# 06_mPCIe_1-4.net
KiCad netlist of a schematic drawn in Altium Designer
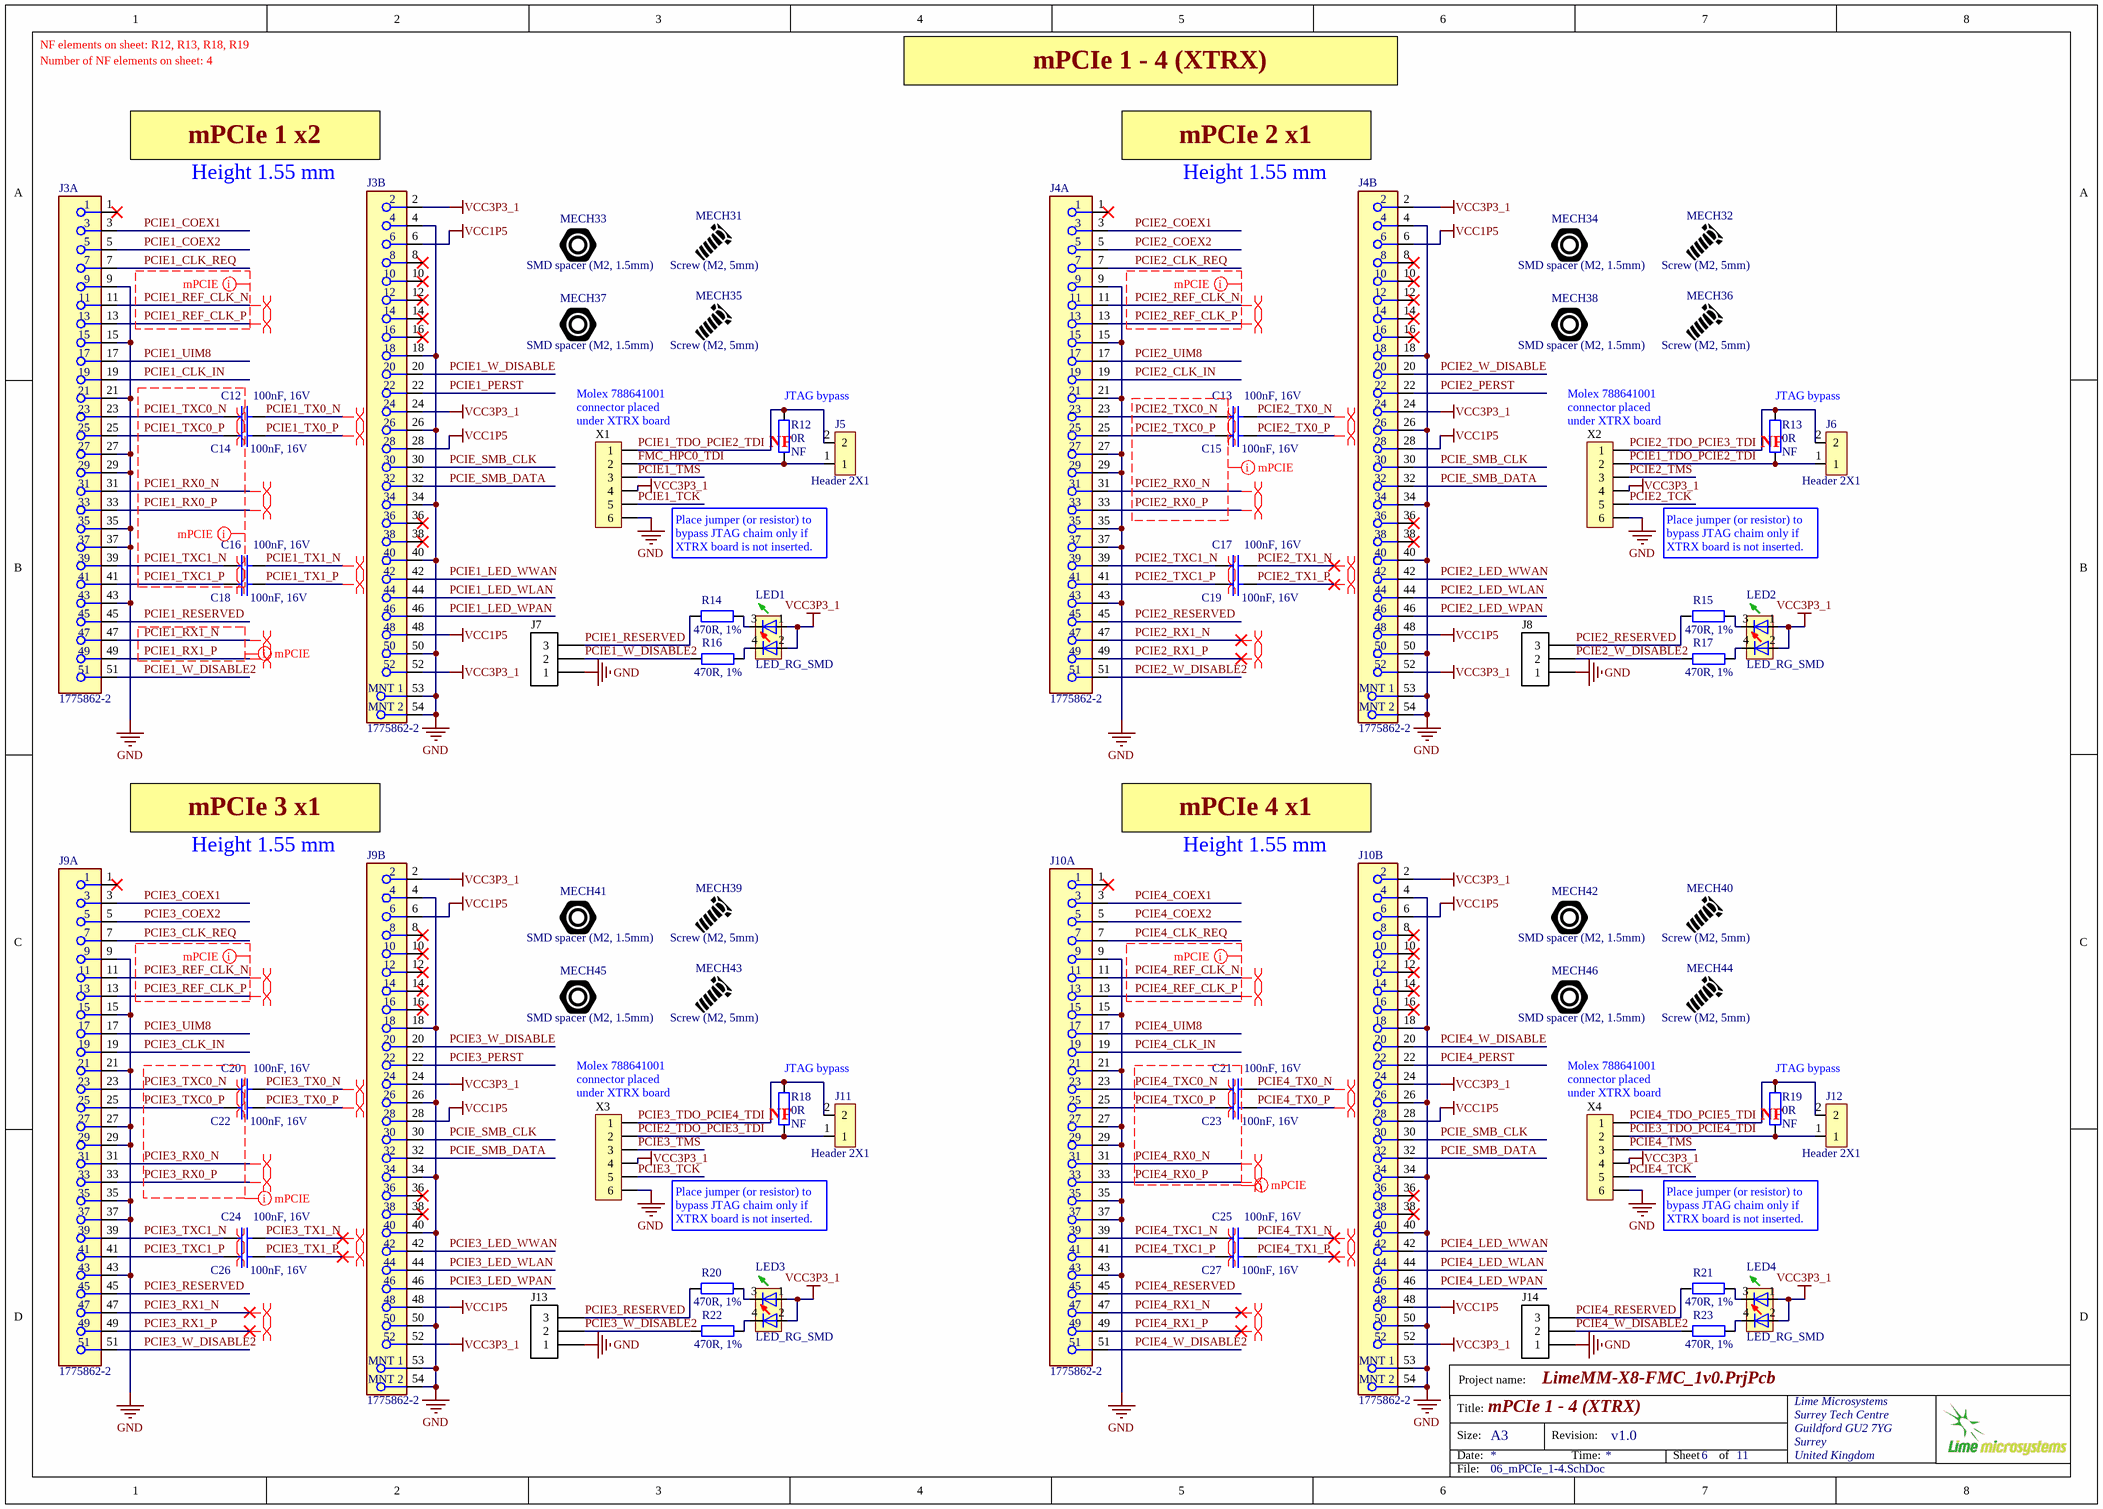
[diagram p0: 06_mPCIe_1-4.SchDoc]

(export (version "E")
  (design (tool "Eeschema 10.0.6"))
  (components
    (comp (ref "C12")
      (value "100nF, 16V")
      (footprint "CAP0402")
      (fields
        (field (name "MANUFACTURER") "Murata Electronics")
        (field (name "TOLERANCE") "10 %")
        (field (name "MANUFACTURER PART NUMBER") "GRM155R71C104KA88D")
      )
      (libsource (lib "LimeMicroAltiumLib_schLib") (part "Cap_0402"))
    )
    (comp (ref "C13")
      (value "100nF, 16V")
      (footprint "CAP0402")
      (fields
        (field (name "MANUFACTURER") "Murata Electronics")
        (field (name "TOLERANCE") "10 %")
        (field (name "MANUFACTURER PART NUMBER") "GRM155R71C104KA88D")
      )
      (libsource (lib "LimeMicroAltiumLib_schLib") (part "Cap_0402"))
    )
    (comp (ref "C14")
      (value "100nF, 16V")
      (footprint "CAP0402")
      (fields
        (field (name "MANUFACTURER") "Murata Electronics")
        (field (name "TOLERANCE") "10 %")
        (field (name "MANUFACTURER PART NUMBER") "GRM155R71C104KA88D")
      )
      (libsource (lib "LimeMicroAltiumLib_schLib") (part "Cap_0402"))
    )
    (comp (ref "C15")
      (value "100nF, 16V")
      (footprint "CAP0402")
      (fields
        (field (name "MANUFACTURER") "Murata Electronics")
        (field (name "TOLERANCE") "10 %")
        (field (name "MANUFACTURER PART NUMBER") "GRM155R71C104KA88D")
      )
      (libsource (lib "LimeMicroAltiumLib_schLib") (part "Cap_0402"))
    )
    (comp (ref "C16")
      (value "100nF, 16V")
      (footprint "CAP0402")
      (fields
        (field (name "MANUFACTURER") "Murata Electronics")
        (field (name "TOLERANCE") "10 %")
        (field (name "MANUFACTURER PART NUMBER") "GRM155R71C104KA88D")
      )
      (libsource (lib "LimeMicroAltiumLib_schLib") (part "Cap_0402"))
    )
    (comp (ref "C17")
      (value "100nF, 16V")
      (footprint "CAP0402")
      (fields
        (field (name "MANUFACTURER") "Murata Electronics")
        (field (name "TOLERANCE") "10 %")
        (field (name "MANUFACTURER PART NUMBER") "GRM155R71C104KA88D")
      )
      (libsource (lib "LimeMicroAltiumLib_schLib") (part "Cap_0402"))
    )
    (comp (ref "C18")
      (value "100nF, 16V")
      (footprint "CAP0402")
      (fields
        (field (name "MANUFACTURER") "Murata Electronics")
        (field (name "TOLERANCE") "10 %")
        (field (name "MANUFACTURER PART NUMBER") "GRM155R71C104KA88D")
      )
      (libsource (lib "LimeMicroAltiumLib_schLib") (part "Cap_0402"))
    )
    (comp (ref "C19")
      (value "100nF, 16V")
      (footprint "CAP0402")
      (fields
        (field (name "MANUFACTURER") "Murata Electronics")
        (field (name "TOLERANCE") "10 %")
        (field (name "MANUFACTURER PART NUMBER") "GRM155R71C104KA88D")
      )
      (libsource (lib "LimeMicroAltiumLib_schLib") (part "Cap_0402"))
    )
    (comp (ref "C20")
      (value "100nF, 16V")
      (footprint "CAP0402")
      (fields
        (field (name "MANUFACTURER") "Murata Electronics")
        (field (name "TOLERANCE") "10 %")
        (field (name "MANUFACTURER PART NUMBER") "GRM155R71C104KA88D")
      )
      (libsource (lib "LimeMicroAltiumLib_schLib") (part "Cap_0402"))
    )
    (comp (ref "C21")
      (value "100nF, 16V")
      (footprint "CAP0402")
      (fields
        (field (name "MANUFACTURER") "Murata Electronics")
        (field (name "TOLERANCE") "10 %")
        (field (name "MANUFACTURER PART NUMBER") "GRM155R71C104KA88D")
      )
      (libsource (lib "LimeMicroAltiumLib_schLib") (part "Cap_0402"))
    )
    (comp (ref "C22")
      (value "100nF, 16V")
      (footprint "CAP0402")
      (fields
        (field (name "MANUFACTURER") "Murata Electronics")
        (field (name "TOLERANCE") "10 %")
        (field (name "MANUFACTURER PART NUMBER") "GRM155R71C104KA88D")
      )
      (libsource (lib "LimeMicroAltiumLib_schLib") (part "Cap_0402"))
    )
    (comp (ref "C23")
      (value "100nF, 16V")
      (footprint "CAP0402")
      (fields
        (field (name "MANUFACTURER") "Murata Electronics")
        (field (name "TOLERANCE") "10 %")
        (field (name "MANUFACTURER PART NUMBER") "GRM155R71C104KA88D")
      )
      (libsource (lib "LimeMicroAltiumLib_schLib") (part "Cap_0402"))
    )
    (comp (ref "C24")
      (value "100nF, 16V")
      (footprint "CAP0402")
      (fields
        (field (name "MANUFACTURER") "Murata Electronics")
        (field (name "TOLERANCE") "10 %")
        (field (name "MANUFACTURER PART NUMBER") "GRM155R71C104KA88D")
      )
      (libsource (lib "LimeMicroAltiumLib_schLib") (part "Cap_0402"))
    )
    (comp (ref "C25")
      (value "100nF, 16V")
      (footprint "CAP0402")
      (fields
        (field (name "MANUFACTURER") "Murata Electronics")
        (field (name "TOLERANCE") "10 %")
        (field (name "MANUFACTURER PART NUMBER") "GRM155R71C104KA88D")
      )
      (libsource (lib "LimeMicroAltiumLib_schLib") (part "Cap_0402"))
    )
    (comp (ref "C26")
      (value "100nF, 16V")
      (footprint "CAP0402")
      (fields
        (field (name "MANUFACTURER") "Murata Electronics")
        (field (name "TOLERANCE") "10 %")
        (field (name "MANUFACTURER PART NUMBER") "GRM155R71C104KA88D")
      )
      (libsource (lib "LimeMicroAltiumLib_schLib") (part "Cap_0402"))
    )
    (comp (ref "C27")
      (value "100nF, 16V")
      (footprint "CAP0402")
      (fields
        (field (name "MANUFACTURER") "Murata Electronics")
        (field (name "TOLERANCE") "10 %")
        (field (name "MANUFACTURER PART NUMBER") "GRM155R71C104KA88D")
      )
      (libsource (lib "LimeMicroAltiumLib_schLib") (part "Cap_0402"))
    )
    (comp (ref "J3")
      (value "1775862-2")
      (footprint "MiniPCIe_connector_XTRX")
      (description "CONN PCI EXP MINI FEMALE 52POS")
      (fields (field (name "MANUFACTURER") "JAE Electronics"))
      (libsource (lib "LimeMicroAltiumLib_schLib_r04") (part "MINI_PCIE_FEMALE"))
    )
    (comp (ref "J4")
      (value "1775862-2")
      (footprint "MiniPCIe_connector_XTRX")
      (description "CONN PCI EXP MINI FEMALE 52POS")
      (fields (field (name "MANUFACTURER") "JAE Electronics"))
      (libsource (lib "LimeMicroAltiumLib_schLib_r04") (part "MINI_PCIE_FEMALE"))
    )
    (comp (ref "J5")
      (value "Header 2X1")
      (footprint "HDR_1x2")
      (fields (field (name "MANUFACTURER") "3M"))
      (libsource (lib "LimeFPGAboard_schLib") (part "Jumper"))
    )
    (comp (ref "J6")
      (value "Header 2X1")
      (footprint "HDR_1x2")
      (fields (field (name "MANUFACTURER") "3M"))
      (libsource (lib "LimeFPGAboard_schLib") (part "Jumper"))
    )
    (comp (ref "J7")
      (value "Header 3x1 pin")
      (footprint "HDR_1x3")
      (description "Header, 3-pin")
      (fields
        (field (name "MANUFACTURER PART NUMBER") "61300311121")
        (field (name "MANUFACTURER") "Wurth Electronics")
      )
      (libsource (lib "LimeMicroAltiumLib_schLib_r04") (part "Header3P"))
    )
    (comp (ref "J8")
      (value "Header 3x1 pin")
      (footprint "HDR_1x3")
      (description "Header, 3-pin")
      (fields
        (field (name "MANUFACTURER PART NUMBER") "61300311121")
        (field (name "MANUFACTURER") "Wurth Electronics")
      )
      (libsource (lib "LimeMicroAltiumLib_schLib_r04") (part "Header3P"))
    )
    (comp (ref "J9")
      (value "1775862-2")
      (footprint "MiniPCIe_connector_XTRX")
      (description "CONN PCI EXP MINI FEMALE 52POS")
      (fields (field (name "MANUFACTURER") "JAE Electronics"))
      (libsource (lib "LimeMicroAltiumLib_schLib_r04") (part "MINI_PCIE_FEMALE"))
    )
    (comp (ref "J10")
      (value "1775862-2")
      (footprint "MiniPCIe_connector_XTRX")
      (description "CONN PCI EXP MINI FEMALE 52POS")
      (fields (field (name "MANUFACTURER") "JAE Electronics"))
      (libsource (lib "LimeMicroAltiumLib_schLib_r04") (part "MINI_PCIE_FEMALE"))
    )
    (comp (ref "J11")
      (value "Header 2X1")
      (footprint "HDR_1x2")
      (fields (field (name "MANUFACTURER") "3M"))
      (libsource (lib "LimeFPGAboard_schLib") (part "Jumper"))
    )
    (comp (ref "J12")
      (value "Header 2X1")
      (footprint "HDR_1x2")
      (fields (field (name "MANUFACTURER") "3M"))
      (libsource (lib "LimeFPGAboard_schLib") (part "Jumper"))
    )
    (comp (ref "J13")
      (value "Header 3x1 pin")
      (footprint "HDR_1x3")
      (description "Header, 3-pin")
      (fields
        (field (name "MANUFACTURER PART NUMBER") "61300311121")
        (field (name "MANUFACTURER") "Wurth Electronics")
      )
      (libsource (lib "LimeMicroAltiumLib_schLib_r04") (part "Header3P"))
    )
    (comp (ref "J14")
      (value "Header 3x1 pin")
      (footprint "HDR_1x3")
      (description "Header, 3-pin")
      (fields
        (field (name "MANUFACTURER PART NUMBER") "61300311121")
        (field (name "MANUFACTURER") "Wurth Electronics")
      )
      (libsource (lib "LimeMicroAltiumLib_schLib_r04") (part "Header3P"))
    )
    (comp (ref "LED1")
      (value "LED_RG_SMD")
      (footprint "LED-2x0603")
      (fields (field (name "MANUFACTURER") "Avago Technologies US Inc."))
      (libsource (lib "LimeMicroAltiumLib_schLib") (part "LED_green_red_SMD"))
    )
    (comp (ref "LED2")
      (value "LED_RG_SMD")
      (footprint "LED-2x0603")
      (fields (field (name "MANUFACTURER") "Avago Technologies US Inc."))
      (libsource (lib "LimeMicroAltiumLib_schLib") (part "LED_green_red_SMD"))
    )
    (comp (ref "LED3")
      (value "LED_RG_SMD")
      (footprint "LED-2x0603")
      (fields (field (name "MANUFACTURER") "Avago Technologies US Inc."))
      (libsource (lib "LimeMicroAltiumLib_schLib") (part "LED_green_red_SMD"))
    )
    (comp (ref "LED4")
      (value "LED_RG_SMD")
      (footprint "LED-2x0603")
      (fields (field (name "MANUFACTURER") "Avago Technologies US Inc."))
      (libsource (lib "LimeMicroAltiumLib_schLib") (part "LED_green_red_SMD"))
    )
    (comp (ref "MECH31")
      (value "Screw (M2, 5mm)")
      (fields (field (name "MANUFACTURER") "B&F Fastener"))
      (libsource (lib "LimeMicroAltiumLib_schLib_r05") (part "Universal_mech_screw"))
    )
    (comp (ref "MECH32")
      (value "Screw (M2, 5mm)")
      (fields (field (name "MANUFACTURER") "B&F Fastener"))
      (libsource (lib "LimeMicroAltiumLib_schLib_r05") (part "Universal_mech_screw"))
    )
    (comp (ref "MECH33")
      (value "SMD spacer (M2, 1.5mm)")
      (fields (field (name "MANUFACTURER") "Wurth Electronics"))
      (libsource (lib "LimeMicroAltiumLib_schLib_r05") (part "Universal_mech_nut"))
    )
    (comp (ref "MECH34")
      (value "SMD spacer (M2, 1.5mm)")
      (fields (field (name "MANUFACTURER") "Wurth Electronics"))
      (libsource (lib "LimeMicroAltiumLib_schLib_r05") (part "Universal_mech_nut"))
    )
    (comp (ref "MECH35")
      (value "Screw (M2, 5mm)")
      (fields (field (name "MANUFACTURER") "B&F Fastener"))
      (libsource (lib "LimeMicroAltiumLib_schLib_r05") (part "Universal_mech_screw"))
    )
    (comp (ref "MECH36")
      (value "Screw (M2, 5mm)")
      (fields (field (name "MANUFACTURER") "B&F Fastener"))
      (libsource (lib "LimeMicroAltiumLib_schLib_r05") (part "Universal_mech_screw"))
    )
    (comp (ref "MECH37")
      (value "SMD spacer (M2, 1.5mm)")
      (fields (field (name "MANUFACTURER") "Wurth Electronics"))
      (libsource (lib "LimeMicroAltiumLib_schLib_r05") (part "Universal_mech_nut"))
    )
    (comp (ref "MECH38")
      (value "SMD spacer (M2, 1.5mm)")
      (fields (field (name "MANUFACTURER") "Wurth Electronics"))
      (libsource (lib "LimeMicroAltiumLib_schLib_r05") (part "Universal_mech_nut"))
    )
    (comp (ref "MECH39")
      (value "Screw (M2, 5mm)")
      (fields (field (name "MANUFACTURER") "B&F Fastener"))
      (libsource (lib "LimeMicroAltiumLib_schLib_r05") (part "Universal_mech_screw"))
    )
    (comp (ref "MECH40")
      (value "Screw (M2, 5mm)")
      (fields (field (name "MANUFACTURER") "B&F Fastener"))
      (libsource (lib "LimeMicroAltiumLib_schLib_r05") (part "Universal_mech_screw"))
    )
    (comp (ref "MECH41")
      (value "SMD spacer (M2, 1.5mm)")
      (fields (field (name "MANUFACTURER") "Wurth Electronics"))
      (libsource (lib "LimeMicroAltiumLib_schLib_r05") (part "Universal_mech_nut"))
    )
    (comp (ref "MECH42")
      (value "SMD spacer (M2, 1.5mm)")
      (fields (field (name "MANUFACTURER") "Wurth Electronics"))
      (libsource (lib "LimeMicroAltiumLib_schLib_r05") (part "Universal_mech_nut"))
    )
    (comp (ref "MECH43")
      (value "Screw (M2, 5mm)")
      (fields (field (name "MANUFACTURER") "B&F Fastener"))
      (libsource (lib "LimeMicroAltiumLib_schLib_r05") (part "Universal_mech_screw"))
    )
    (comp (ref "MECH44")
      (value "Screw (M2, 5mm)")
      (fields (field (name "MANUFACTURER") "B&F Fastener"))
      (libsource (lib "LimeMicroAltiumLib_schLib_r05") (part "Universal_mech_screw"))
    )
    (comp (ref "MECH45")
      (value "SMD spacer (M2, 1.5mm)")
      (fields (field (name "MANUFACTURER") "Wurth Electronics"))
      (libsource (lib "LimeMicroAltiumLib_schLib_r05") (part "Universal_mech_nut"))
    )
    (comp (ref "MECH46")
      (value "SMD spacer (M2, 1.5mm)")
      (fields (field (name "MANUFACTURER") "Wurth Electronics"))
      (libsource (lib "LimeMicroAltiumLib_schLib_r05") (part "Universal_mech_nut"))
    )
    (comp (ref "R12")
      (value "0R")
      (footprint "RES0402")
      (fields
        (field (name "ASSEMBLY INFO") "NF")
        (field (name "MANUFACTURER") "Yageo")
        (field (name "TOLERANCE") "Jumper")
      )
      (libsource (lib "") (part "Res_0402_1"))
    )
    (comp (ref "R13")
      (value "0R")
      (footprint "RES0402")
      (fields
        (field (name "ASSEMBLY INFO") "NF")
        (field (name "MANUFACTURER") "Yageo")
        (field (name "TOLERANCE") "Jumper")
      )
      (libsource (lib "") (part "Res_0402_1"))
    )
    (comp (ref "R14")
      (value "470R, 1%")
      (footprint "RES0402")
      (fields (field (name "TOLERANCE") "1%") (field (name "MANUFACTURER") "Yageo"))
      (libsource (lib "LimeMicroAltiumLib_schLib") (part "Res_0402"))
    )
    (comp (ref "R15")
      (value "470R, 1%")
      (footprint "RES0402")
      (fields (field (name "TOLERANCE") "1%") (field (name "MANUFACTURER") "Yageo"))
      (libsource (lib "LimeMicroAltiumLib_schLib") (part "Res_0402"))
    )
    (comp (ref "R16")
      (value "470R, 1%")
      (footprint "RES0402")
      (fields (field (name "TOLERANCE") "1%") (field (name "MANUFACTURER") "Yageo"))
      (libsource (lib "LimeMicroAltiumLib_schLib") (part "Res_0402"))
    )
    (comp (ref "R17")
      (value "470R, 1%")
      (footprint "RES0402")
      (fields (field (name "TOLERANCE") "1%") (field (name "MANUFACTURER") "Yageo"))
      (libsource (lib "LimeMicroAltiumLib_schLib") (part "Res_0402"))
    )
    (comp (ref "R18")
      (value "0R")
      (footprint "RES0402")
      (fields
        (field (name "ASSEMBLY INFO") "NF")
        (field (name "MANUFACTURER") "Yageo")
        (field (name "TOLERANCE") "Jumper")
      )
      (libsource (lib "") (part "Res_0402_1"))
    )
    (comp (ref "R19")
      (value "0R")
      (footprint "RES0402")
      (fields
        (field (name "ASSEMBLY INFO") "NF")
        (field (name "MANUFACTURER") "Yageo")
        (field (name "TOLERANCE") "Jumper")
      )
      (libsource (lib "") (part "Res_0402_1"))
    )
    (comp (ref "R20")
      (value "470R, 1%")
      (footprint "RES0402")
      (fields (field (name "TOLERANCE") "1%") (field (name "MANUFACTURER") "Yageo"))
      (libsource (lib "LimeMicroAltiumLib_schLib") (part "Res_0402"))
    )
    (comp (ref "R21")
      (value "470R, 1%")
      (footprint "RES0402")
      (fields (field (name "TOLERANCE") "1%") (field (name "MANUFACTURER") "Yageo"))
      (libsource (lib "LimeMicroAltiumLib_schLib") (part "Res_0402"))
    )
    (comp (ref "R22")
      (value "470R, 1%")
      (footprint "RES0402")
      (fields (field (name "TOLERANCE") "1%") (field (name "MANUFACTURER") "Yageo"))
      (libsource (lib "LimeMicroAltiumLib_schLib") (part "Res_0402"))
    )
    (comp (ref "R23")
      (value "470R, 1%")
      (footprint "RES0402")
      (fields (field (name "TOLERANCE") "1%") (field (name "MANUFACTURER") "Yageo"))
      (libsource (lib "LimeMicroAltiumLib_schLib") (part "Res_0402"))
    )
    (comp (ref "X1")
      (value "Molex 0788641001")
      (footprint "Molex_0788641001_spring_contacts_carrier")
      (description "Header, 6-pin")
      (fields (field (name "MANUFACTURER") "Molex"))
      (libsource (lib "LimeMicroAltiumLib_schLib_r04") (part "Molex_0788641001_spring_contacts"))
    )
    (comp (ref "X2")
      (value "Molex 0788641001")
      (footprint "Molex_0788641001_spring_contacts_carrier")
      (description "Header, 6-pin")
      (fields (field (name "MANUFACTURER") "Molex"))
      (libsource (lib "LimeMicroAltiumLib_schLib_r04") (part "Molex_0788641001_spring_contacts"))
    )
    (comp (ref "X3")
      (value "Molex 0788641001")
      (footprint "Molex_0788641001_spring_contacts_carrier")
      (description "Header, 6-pin")
      (fields (field (name "MANUFACTURER") "Molex"))
      (libsource (lib "LimeMicroAltiumLib_schLib_r04") (part "Molex_0788641001_spring_contacts"))
    )
    (comp (ref "X4")
      (value "Molex 0788641001")
      (footprint "Molex_0788641001_spring_contacts_carrier")
      (description "Header, 6-pin")
      (fields (field (name "MANUFACTURER") "Molex"))
      (libsource (lib "LimeMicroAltiumLib_schLib_r04") (part "Molex_0788641001_spring_contacts"))
    )
  )
  (nets
    (net (code "1") (name "/FMC_HPC0_TDI") (class "Default")
      (node (ref "J5") (pin "1") (pinfunction "1_1") (pintype "passive"))
      (node (ref "R12") (pin "2") (pinfunction "2_2") (pintype "passive"))
      (node (ref "X1") (pin "2") (pinfunction "2_2") (pintype "passive"))
    )
    (net (code "2") (name "/PCIE1_CLK_IN") (class "Default")
      (node (ref "J3") (pin "19") (pinfunction "19_19") (pintype "passive"))
    )
    (net (code "3") (name "/PCIE1_CLK_REQ") (class "Default")
      (node (ref "J3") (pin "7") (pinfunction "7_7") (pintype "passive"))
    )
    (net (code "4") (name "/PCIE1_COEX1") (class "Default")
      (node (ref "J3") (pin "3") (pinfunction "3_3") (pintype "passive"))
    )
    (net (code "5") (name "/PCIE1_COEX2") (class "Default")
      (node (ref "J3") (pin "5") (pinfunction "5_5") (pintype "passive"))
    )
    (net (code "6") (name "/PCIE1_LED_WLAN") (class "Default")
      (node (ref "J3") (pin "44") (pinfunction "44_44") (pintype "passive"))
    )
    (net (code "7") (name "/PCIE1_LED_WPAN") (class "Default")
      (node (ref "J3") (pin "46") (pinfunction "46_46") (pintype "passive"))
    )
    (net (code "8") (name "/PCIE1_LED_WWAN") (class "Default")
      (node (ref "J3") (pin "42") (pinfunction "42_42") (pintype "passive"))
    )
    (net (code "9") (name "/PCIE1_PERST") (class "Default")
      (node (ref "J3") (pin "22") (pinfunction "22_22") (pintype "passive"))
    )
    (net (code "10") (name "/PCIE1_REF_CLK_N") (class "Default")
      (node (ref "J3") (pin "11") (pinfunction "11_11") (pintype "passive"))
    )
    (net (code "11") (name "/PCIE1_REF_CLK_P") (class "Default")
      (node (ref "J3") (pin "13") (pinfunction "13_13") (pintype "passive"))
    )
    (net (code "12") (name "/PCIE1_RESERVED") (class "Default")
      (node (ref "J3") (pin "45") (pinfunction "45_45") (pintype "passive"))
      (node (ref "J7") (pin "3") (pinfunction "3_3") (pintype "passive"))
      (node (ref "R14") (pin "2") (pinfunction "2_2") (pintype "passive"))
    )
    (net (code "13") (name "/PCIE1_RX0_N") (class "Default")
      (node (ref "J3") (pin "31") (pinfunction "31_31") (pintype "passive"))
    )
    (net (code "14") (name "/PCIE1_RX0_P") (class "Default")
      (node (ref "J3") (pin "33") (pinfunction "33_33") (pintype "passive"))
    )
    (net (code "15") (name "/PCIE1_RX1_N") (class "Default")
      (node (ref "J3") (pin "47") (pinfunction "47_47") (pintype "passive"))
    )
    (net (code "16") (name "/PCIE1_RX1_P") (class "Default")
      (node (ref "J3") (pin "49") (pinfunction "49_49") (pintype "passive"))
    )
    (net (code "17") (name "/PCIE1_TCK") (class "Default")
      (node (ref "X1") (pin "5") (pinfunction "5_5") (pintype "passive"))
    )
    (net (code "18") (name "/PCIE1_TDO_PCIE2_TDI") (class "Default")
      (node (ref "J5") (pin "2") (pinfunction "2_2") (pintype "passive"))
      (node (ref "J6") (pin "1") (pinfunction "1_1") (pintype "passive"))
      (node (ref "R12") (pin "1") (pinfunction "1_1") (pintype "passive"))
      (node (ref "R13") (pin "2") (pinfunction "2_2") (pintype "passive"))
      (node (ref "X1") (pin "1") (pinfunction "1_1") (pintype "passive"))
      (node (ref "X2") (pin "2") (pinfunction "2_2") (pintype "passive"))
    )
    (net (code "19") (name "/PCIE1_TMS") (class "Default")
      (node (ref "X1") (pin "3") (pinfunction "3_3") (pintype "passive"))
    )
    (net (code "20") (name "/PCIE1_TX0_N") (class "Default")
      (node (ref "C12") (pin "1") (pinfunction "1_1") (pintype "passive"))
    )
    (net (code "21") (name "/PCIE1_TX0_P") (class "Default")
      (node (ref "C14") (pin "1") (pinfunction "1_1") (pintype "passive"))
    )
    (net (code "22") (name "/PCIE1_TX1_N") (class "Default")
      (node (ref "C16") (pin "1") (pinfunction "1_1") (pintype "passive"))
    )
    (net (code "23") (name "/PCIE1_TX1_P") (class "Default")
      (node (ref "C18") (pin "1") (pinfunction "1_1") (pintype "passive"))
    )
    (net (code "24") (name "/PCIE1_TXC0_N") (class "Default")
      (node (ref "C12") (pin "2") (pinfunction "2_2") (pintype "passive"))
      (node (ref "J3") (pin "23") (pinfunction "23_23") (pintype "passive"))
    )
    (net (code "25") (name "/PCIE1_TXC0_P") (class "Default")
      (node (ref "C14") (pin "2") (pinfunction "2_2") (pintype "passive"))
      (node (ref "J3") (pin "25") (pinfunction "25_25") (pintype "passive"))
    )
    (net (code "26") (name "/PCIE1_TXC1_N") (class "Default")
      (node (ref "C16") (pin "2") (pinfunction "2_2") (pintype "passive"))
      (node (ref "J3") (pin "39") (pinfunction "39_39") (pintype "passive"))
    )
    (net (code "27") (name "/PCIE1_TXC1_P") (class "Default")
      (node (ref "C18") (pin "2") (pinfunction "2_2") (pintype "passive"))
      (node (ref "J3") (pin "41") (pinfunction "41_41") (pintype "passive"))
    )
    (net (code "28") (name "/PCIE1_UIM8") (class "Default")
      (node (ref "J3") (pin "17") (pinfunction "17_17") (pintype "passive"))
    )
    (net (code "29") (name "/PCIE1_W_DISABLE") (class "Default")
      (node (ref "J3") (pin "20") (pinfunction "20_20") (pintype "passive"))
    )
    (net (code "30") (name "/PCIE1_W_DISABLE2") (class "Default")
      (node (ref "J3") (pin "51") (pinfunction "51_51") (pintype "passive"))
      (node (ref "J7") (pin "2") (pinfunction "2_2") (pintype "passive"))
      (node (ref "R16") (pin "2") (pinfunction "2_2") (pintype "passive"))
    )
    (net (code "31") (name "/PCIE2_CLK_IN") (class "Default")
      (node (ref "J4") (pin "19") (pinfunction "19_19") (pintype "passive"))
    )
    (net (code "32") (name "/PCIE2_CLK_REQ") (class "Default")
      (node (ref "J4") (pin "7") (pinfunction "7_7") (pintype "passive"))
    )
    (net (code "33") (name "/PCIE2_COEX1") (class "Default")
      (node (ref "J4") (pin "3") (pinfunction "3_3") (pintype "passive"))
    )
    (net (code "34") (name "/PCIE2_COEX2") (class "Default")
      (node (ref "J4") (pin "5") (pinfunction "5_5") (pintype "passive"))
    )
    (net (code "35") (name "/PCIE2_LED_WLAN") (class "Default")
      (node (ref "J4") (pin "44") (pinfunction "44_44") (pintype "passive"))
    )
    (net (code "36") (name "/PCIE2_LED_WPAN") (class "Default")
      (node (ref "J4") (pin "46") (pinfunction "46_46") (pintype "passive"))
    )
    (net (code "37") (name "/PCIE2_LED_WWAN") (class "Default")
      (node (ref "J4") (pin "42") (pinfunction "42_42") (pintype "passive"))
    )
    (net (code "38") (name "/PCIE2_PERST") (class "Default")
      (node (ref "J4") (pin "22") (pinfunction "22_22") (pintype "passive"))
    )
    (net (code "39") (name "/PCIE2_REF_CLK_N") (class "Default")
      (node (ref "J4") (pin "11") (pinfunction "11_11") (pintype "passive"))
    )
    (net (code "40") (name "/PCIE2_REF_CLK_P") (class "Default")
      (node (ref "J4") (pin "13") (pinfunction "13_13") (pintype "passive"))
    )
    (net (code "41") (name "/PCIE2_RESERVED") (class "Default")
      (node (ref "J4") (pin "45") (pinfunction "45_45") (pintype "passive"))
      (node (ref "J8") (pin "3") (pinfunction "3_3") (pintype "passive"))
      (node (ref "R15") (pin "2") (pinfunction "2_2") (pintype "passive"))
    )
    (net (code "42") (name "/PCIE2_RX0_N") (class "Default")
      (node (ref "J4") (pin "31") (pinfunction "31_31") (pintype "passive"))
    )
    (net (code "43") (name "/PCIE2_RX0_P") (class "Default")
      (node (ref "J4") (pin "33") (pinfunction "33_33") (pintype "passive"))
    )
    (net (code "44") (name "/PCIE2_RX1_N") (class "Default")
      (node (ref "J4") (pin "47") (pinfunction "47_47") (pintype "passive+no_connect"))
    )
    (net (code "45") (name "/PCIE2_RX1_P") (class "Default")
      (node (ref "J4") (pin "49") (pinfunction "49_49") (pintype "passive+no_connect"))
    )
    (net (code "46") (name "/PCIE2_TCK") (class "Default")
      (node (ref "X2") (pin "5") (pinfunction "5_5") (pintype "passive"))
    )
    (net (code "47") (name "/PCIE2_TDO_PCIE3_TDI") (class "Default")
      (node (ref "J11") (pin "1") (pinfunction "1_1") (pintype "passive"))
      (node (ref "J6") (pin "2") (pinfunction "2_2") (pintype "passive"))
      (node (ref "R13") (pin "1") (pinfunction "1_1") (pintype "passive"))
      (node (ref "R18") (pin "2") (pinfunction "2_2") (pintype "passive"))
      (node (ref "X2") (pin "1") (pinfunction "1_1") (pintype "passive"))
      (node (ref "X3") (pin "2") (pinfunction "2_2") (pintype "passive"))
    )
    (net (code "48") (name "/PCIE2_TMS") (class "Default")
      (node (ref "X2") (pin "3") (pinfunction "3_3") (pintype "passive"))
    )
    (net (code "49") (name "/PCIE2_TX0_N") (class "Default")
      (node (ref "C13") (pin "1") (pinfunction "1_1") (pintype "passive"))
    )
    (net (code "50") (name "/PCIE2_TX0_P") (class "Default")
      (node (ref "C15") (pin "1") (pinfunction "1_1") (pintype "passive"))
    )
    (net (code "51") (name "/PCIE2_TX1_N") (class "Default")
      (node (ref "C17") (pin "1") (pinfunction "1_1") (pintype "passive+no_connect"))
    )
    (net (code "52") (name "/PCIE2_TX1_P") (class "Default")
      (node (ref "C19") (pin "1") (pinfunction "1_1") (pintype "passive+no_connect"))
    )
    (net (code "53") (name "/PCIE2_TXC0_N") (class "Default")
      (node (ref "C13") (pin "2") (pinfunction "2_2") (pintype "passive"))
      (node (ref "J4") (pin "23") (pinfunction "23_23") (pintype "passive"))
    )
    (net (code "54") (name "/PCIE2_TXC0_P") (class "Default")
      (node (ref "C15") (pin "2") (pinfunction "2_2") (pintype "passive"))
      (node (ref "J4") (pin "25") (pinfunction "25_25") (pintype "passive"))
    )
    (net (code "55") (name "/PCIE2_TXC1_N") (class "Default")
      (node (ref "C17") (pin "2") (pinfunction "2_2") (pintype "passive"))
      (node (ref "J4") (pin "39") (pinfunction "39_39") (pintype "passive"))
    )
    (net (code "56") (name "/PCIE2_TXC1_P") (class "Default")
      (node (ref "C19") (pin "2") (pinfunction "2_2") (pintype "passive"))
      (node (ref "J4") (pin "41") (pinfunction "41_41") (pintype "passive"))
    )
    (net (code "57") (name "/PCIE2_UIM8") (class "Default")
      (node (ref "J4") (pin "17") (pinfunction "17_17") (pintype "passive"))
    )
    (net (code "58") (name "/PCIE2_W_DISABLE") (class "Default")
      (node (ref "J4") (pin "20") (pinfunction "20_20") (pintype "passive"))
    )
    (net (code "59") (name "/PCIE2_W_DISABLE2") (class "Default")
      (node (ref "J4") (pin "51") (pinfunction "51_51") (pintype "passive"))
      (node (ref "J8") (pin "2") (pinfunction "2_2") (pintype "passive"))
      (node (ref "R17") (pin "2") (pinfunction "2_2") (pintype "passive"))
    )
    (net (code "60") (name "/PCIE3_CLK_IN") (class "Default")
      (node (ref "J9") (pin "19") (pinfunction "19_19") (pintype "passive"))
    )
    (net (code "61") (name "/PCIE3_CLK_REQ") (class "Default")
      (node (ref "J9") (pin "7") (pinfunction "7_7") (pintype "passive"))
    )
    (net (code "62") (name "/PCIE3_COEX1") (class "Default")
      (node (ref "J9") (pin "3") (pinfunction "3_3") (pintype "passive"))
    )
    (net (code "63") (name "/PCIE3_COEX2") (class "Default")
      (node (ref "J9") (pin "5") (pinfunction "5_5") (pintype "passive"))
    )
    (net (code "64") (name "/PCIE3_LED_WLAN") (class "Default")
      (node (ref "J9") (pin "44") (pinfunction "44_44") (pintype "passive"))
    )
    (net (code "65") (name "/PCIE3_LED_WPAN") (class "Default")
      (node (ref "J9") (pin "46") (pinfunction "46_46") (pintype "passive"))
    )
    (net (code "66") (name "/PCIE3_LED_WWAN") (class "Default")
      (node (ref "J9") (pin "42") (pinfunction "42_42") (pintype "passive"))
    )
    (net (code "67") (name "/PCIE3_PERST") (class "Default")
      (node (ref "J9") (pin "22") (pinfunction "22_22") (pintype "passive"))
    )
    (net (code "68") (name "/PCIE3_REF_CLK_N") (class "Default")
      (node (ref "J9") (pin "11") (pinfunction "11_11") (pintype "passive"))
    )
    (net (code "69") (name "/PCIE3_REF_CLK_P") (class "Default")
      (node (ref "J9") (pin "13") (pinfunction "13_13") (pintype "passive"))
    )
    (net (code "70") (name "/PCIE3_RESERVED") (class "Default")
      (node (ref "J13") (pin "3") (pinfunction "3_3") (pintype "passive"))
      (node (ref "J9") (pin "45") (pinfunction "45_45") (pintype "passive"))
      (node (ref "R20") (pin "2") (pinfunction "2_2") (pintype "passive"))
    )
    (net (code "71") (name "/PCIE3_RX0_N") (class "Default")
      (node (ref "J9") (pin "31") (pinfunction "31_31") (pintype "passive"))
    )
    (net (code "72") (name "/PCIE3_RX0_P") (class "Default")
      (node (ref "J9") (pin "33") (pinfunction "33_33") (pintype "passive"))
    )
    (net (code "73") (name "/PCIE3_RX1_N") (class "Default")
      (node (ref "J9") (pin "47") (pinfunction "47_47") (pintype "passive+no_connect"))
    )
    (net (code "74") (name "/PCIE3_RX1_P") (class "Default")
      (node (ref "J9") (pin "49") (pinfunction "49_49") (pintype "passive+no_connect"))
    )
    (net (code "75") (name "/PCIE3_TCK") (class "Default")
      (node (ref "X3") (pin "5") (pinfunction "5_5") (pintype "passive"))
    )
    (net (code "76") (name "/PCIE3_TDO_PCIE4_TDI") (class "Default")
      (node (ref "J11") (pin "2") (pinfunction "2_2") (pintype "passive"))
      (node (ref "J12") (pin "1") (pinfunction "1_1") (pintype "passive"))
      (node (ref "R18") (pin "1") (pinfunction "1_1") (pintype "passive"))
      (node (ref "R19") (pin "2") (pinfunction "2_2") (pintype "passive"))
      (node (ref "X3") (pin "1") (pinfunction "1_1") (pintype "passive"))
      (node (ref "X4") (pin "2") (pinfunction "2_2") (pintype "passive"))
    )
    (net (code "77") (name "/PCIE3_TMS") (class "Default")
      (node (ref "X3") (pin "3") (pinfunction "3_3") (pintype "passive"))
    )
    (net (code "78") (name "/PCIE3_TX0_N") (class "Default")
      (node (ref "C20") (pin "1") (pinfunction "1_1") (pintype "passive"))
    )
    (net (code "79") (name "/PCIE3_TX0_P") (class "Default")
      (node (ref "C22") (pin "1") (pinfunction "1_1") (pintype "passive"))
    )
    (net (code "80") (name "/PCIE3_TX1_N") (class "Default")
      (node (ref "C24") (pin "1") (pinfunction "1_1") (pintype "passive+no_connect"))
    )
    (net (code "81") (name "/PCIE3_TX1_P") (class "Default")
      (node (ref "C26") (pin "1") (pinfunction "1_1") (pintype "passive+no_connect"))
    )
    (net (code "82") (name "/PCIE3_TXC0_N") (class "Default")
      (node (ref "C20") (pin "2") (pinfunction "2_2") (pintype "passive"))
      (node (ref "J9") (pin "23") (pinfunction "23_23") (pintype "passive"))
    )
    (net (code "83") (name "/PCIE3_TXC0_P") (class "Default")
      (node (ref "C22") (pin "2") (pinfunction "2_2") (pintype "passive"))
      (node (ref "J9") (pin "25") (pinfunction "25_25") (pintype "passive"))
    )
    (net (code "84") (name "/PCIE3_TXC1_N") (class "Default")
      (node (ref "C24") (pin "2") (pinfunction "2_2") (pintype "passive"))
      (node (ref "J9") (pin "39") (pinfunction "39_39") (pintype "passive"))
    )
    (net (code "85") (name "/PCIE3_TXC1_P") (class "Default")
      (node (ref "C26") (pin "2") (pinfunction "2_2") (pintype "passive"))
      (node (ref "J9") (pin "41") (pinfunction "41_41") (pintype "passive"))
    )
    (net (code "86") (name "/PCIE3_UIM8") (class "Default")
      (node (ref "J9") (pin "17") (pinfunction "17_17") (pintype "passive"))
    )
    (net (code "87") (name "/PCIE3_W_DISABLE") (class "Default")
      (node (ref "J9") (pin "20") (pinfunction "20_20") (pintype "passive"))
    )
    (net (code "88") (name "/PCIE3_W_DISABLE2") (class "Default")
      (node (ref "J13") (pin "2") (pinfunction "2_2") (pintype "passive"))
      (node (ref "J9") (pin "51") (pinfunction "51_51") (pintype "passive"))
      (node (ref "R22") (pin "2") (pinfunction "2_2") (pintype "passive"))
    )
    (net (code "89") (name "/PCIE4_CLK_IN") (class "Default")
      (node (ref "J10") (pin "19") (pinfunction "19_19") (pintype "passive"))
    )
    (net (code "90") (name "/PCIE4_CLK_REQ") (class "Default")
      (node (ref "J10") (pin "7") (pinfunction "7_7") (pintype "passive"))
    )
    (net (code "91") (name "/PCIE4_COEX1") (class "Default")
      (node (ref "J10") (pin "3") (pinfunction "3_3") (pintype "passive"))
    )
    (net (code "92") (name "/PCIE4_COEX2") (class "Default")
      (node (ref "J10") (pin "5") (pinfunction "5_5") (pintype "passive"))
    )
    (net (code "93") (name "/PCIE4_LED_WLAN") (class "Default")
      (node (ref "J10") (pin "44") (pinfunction "44_44") (pintype "passive"))
    )
    (net (code "94") (name "/PCIE4_LED_WPAN") (class "Default")
      (node (ref "J10") (pin "46") (pinfunction "46_46") (pintype "passive"))
    )
    (net (code "95") (name "/PCIE4_LED_WWAN") (class "Default")
      (node (ref "J10") (pin "42") (pinfunction "42_42") (pintype "passive"))
    )
    (net (code "96") (name "/PCIE4_PERST") (class "Default")
      (node (ref "J10") (pin "22") (pinfunction "22_22") (pintype "passive"))
    )
    (net (code "97") (name "/PCIE4_REF_CLK_N") (class "Default")
      (node (ref "J10") (pin "11") (pinfunction "11_11") (pintype "passive"))
    )
    (net (code "98") (name "/PCIE4_REF_CLK_P") (class "Default")
      (node (ref "J10") (pin "13") (pinfunction "13_13") (pintype "passive"))
    )
    (net (code "99") (name "/PCIE4_RESERVED") (class "Default")
      (node (ref "J10") (pin "45") (pinfunction "45_45") (pintype "passive"))
      (node (ref "J14") (pin "3") (pinfunction "3_3") (pintype "passive"))
      (node (ref "R21") (pin "2") (pinfunction "2_2") (pintype "passive"))
    )
    (net (code "100") (name "/PCIE4_RX0_N") (class "Default")
      (node (ref "J10") (pin "31") (pinfunction "31_31") (pintype "passive"))
    )
    (net (code "101") (name "/PCIE4_RX0_P") (class "Default")
      (node (ref "J10") (pin "33") (pinfunction "33_33") (pintype "passive"))
    )
    (net (code "102") (name "/PCIE4_RX1_N") (class "Default")
      (node (ref "J10") (pin "47") (pinfunction "47_47") (pintype "passive+no_connect"))
    )
    (net (code "103") (name "/PCIE4_RX1_P") (class "Default")
      (node (ref "J10") (pin "49") (pinfunction "49_49") (pintype "passive+no_connect"))
    )
    (net (code "104") (name "/PCIE4_TCK") (class "Default")
      (node (ref "X4") (pin "5") (pinfunction "5_5") (pintype "passive"))
    )
    (net (code "105") (name "/PCIE4_TDO_PCIE5_TDI") (class "Default")
      (node (ref "J12") (pin "2") (pinfunction "2_2") (pintype "passive"))
      (node (ref "R19") (pin "1") (pinfunction "1_1") (pintype "passive"))
      (node (ref "X4") (pin "1") (pinfunction "1_1") (pintype "passive"))
    )
    (net (code "106") (name "/PCIE4_TMS") (class "Default")
      (node (ref "X4") (pin "3") (pinfunction "3_3") (pintype "passive"))
    )
    (net (code "107") (name "/PCIE4_TX0_N") (class "Default")
      (node (ref "C21") (pin "1") (pinfunction "1_1") (pintype "passive"))
    )
    (net (code "108") (name "/PCIE4_TX0_P") (class "Default")
      (node (ref "C23") (pin "1") (pinfunction "1_1") (pintype "passive"))
    )
    (net (code "109") (name "/PCIE4_TX1_N") (class "Default")
      (node (ref "C25") (pin "1") (pinfunction "1_1") (pintype "passive+no_connect"))
    )
    (net (code "110") (name "/PCIE4_TX1_P") (class "Default")
      (node (ref "C27") (pin "1") (pinfunction "1_1") (pintype "passive+no_connect"))
    )
    (net (code "111") (name "/PCIE4_TXC0_N") (class "Default")
      (node (ref "C21") (pin "2") (pinfunction "2_2") (pintype "passive"))
      (node (ref "J10") (pin "23") (pinfunction "23_23") (pintype "passive"))
    )
    (net (code "112") (name "/PCIE4_TXC0_P") (class "Default")
      (node (ref "C23") (pin "2") (pinfunction "2_2") (pintype "passive"))
      (node (ref "J10") (pin "25") (pinfunction "25_25") (pintype "passive"))
    )
    (net (code "113") (name "/PCIE4_TXC1_N") (class "Default")
      (node (ref "C25") (pin "2") (pinfunction "2_2") (pintype "passive"))
      (node (ref "J10") (pin "39") (pinfunction "39_39") (pintype "passive"))
    )
    (net (code "114") (name "/PCIE4_TXC1_P") (class "Default")
      (node (ref "C27") (pin "2") (pinfunction "2_2") (pintype "passive"))
      (node (ref "J10") (pin "41") (pinfunction "41_41") (pintype "passive"))
    )
    (net (code "115") (name "/PCIE4_UIM8") (class "Default")
      (node (ref "J10") (pin "17") (pinfunction "17_17") (pintype "passive"))
    )
    (net (code "116") (name "/PCIE4_W_DISABLE") (class "Default")
      (node (ref "J10") (pin "20") (pinfunction "20_20") (pintype "passive"))
    )
    (net (code "117") (name "/PCIE4_W_DISABLE2") (class "Default")
      (node (ref "J10") (pin "51") (pinfunction "51_51") (pintype "passive"))
      (node (ref "J14") (pin "2") (pinfunction "2_2") (pintype "passive"))
      (node (ref "R23") (pin "2") (pinfunction "2_2") (pintype "passive"))
    )
    (net (code "118") (name "/PCIE_SMB_CLK") (class "Default")
      (node (ref "J10") (pin "30") (pinfunction "30_30") (pintype "passive"))
      (node (ref "J3") (pin "30") (pinfunction "30_30") (pintype "passive"))
      (node (ref "J4") (pin "30") (pinfunction "30_30") (pintype "passive"))
      (node (ref "J9") (pin "30") (pinfunction "30_30") (pintype "passive"))
    )
    (net (code "119") (name "/PCIE_SMB_DATA") (class "Default")
      (node (ref "J10") (pin "32") (pinfunction "32_32") (pintype "passive"))
      (node (ref "J3") (pin "32") (pinfunction "32_32") (pintype "passive"))
      (node (ref "J4") (pin "32") (pinfunction "32_32") (pintype "passive"))
      (node (ref "J9") (pin "32") (pinfunction "32_32") (pintype "passive"))
    )
    (net (code "120") (name "GND") (class "Default")
      (node (ref "J10") (pin "15") (pinfunction "15_15") (pintype "passive"))
      (node (ref "J10") (pin "18") (pinfunction "18_18") (pintype "passive"))
      (node (ref "J10") (pin "21") (pinfunction "21_21") (pintype "passive"))
      (node (ref "J10") (pin "26") (pinfunction "26_26") (pintype "passive"))
      (node (ref "J10") (pin "27") (pinfunction "27_27") (pintype "passive"))
      (node (ref "J10") (pin "29") (pinfunction "29_29") (pintype "passive"))
      (node (ref "J10") (pin "34") (pinfunction "34_34") (pintype "passive"))
      (node (ref "J10") (pin "35") (pinfunction "35_35") (pintype "passive"))
      (node (ref "J10") (pin "37") (pinfunction "37_37") (pintype "passive"))
      (node (ref "J10") (pin "4") (pinfunction "4_4") (pintype "passive"))
      (node (ref "J10") (pin "40") (pinfunction "40_40") (pintype "passive"))
      (node (ref "J10") (pin "43") (pinfunction "43_43") (pintype "passive"))
      (node (ref "J10") (pin "50") (pinfunction "50_50") (pintype "passive"))
      (node (ref "J10") (pin "53") (pinfunction "MNT_1_53") (pintype "passive"))
      (node (ref "J10") (pin "54") (pinfunction "MNT_2_54") (pintype "passive"))
      (node (ref "J10") (pin "9") (pinfunction "9_9") (pintype "passive"))
      (node (ref "J13") (pin "1") (pinfunction "1_1") (pintype "passive"))
      (node (ref "J14") (pin "1") (pinfunction "1_1") (pintype "passive"))
      (node (ref "J3") (pin "15") (pinfunction "15_15") (pintype "passive"))
      (node (ref "J3") (pin "18") (pinfunction "18_18") (pintype "passive"))
      (node (ref "J3") (pin "21") (pinfunction "21_21") (pintype "passive"))
      (node (ref "J3") (pin "26") (pinfunction "26_26") (pintype "passive"))
      (node (ref "J3") (pin "27") (pinfunction "27_27") (pintype "passive"))
      (node (ref "J3") (pin "29") (pinfunction "29_29") (pintype "passive"))
      (node (ref "J3") (pin "34") (pinfunction "34_34") (pintype "passive"))
      (node (ref "J3") (pin "35") (pinfunction "35_35") (pintype "passive"))
      (node (ref "J3") (pin "37") (pinfunction "37_37") (pintype "passive"))
      (node (ref "J3") (pin "4") (pinfunction "4_4") (pintype "passive"))
      (node (ref "J3") (pin "40") (pinfunction "40_40") (pintype "passive"))
      (node (ref "J3") (pin "43") (pinfunction "43_43") (pintype "passive"))
      (node (ref "J3") (pin "50") (pinfunction "50_50") (pintype "passive"))
      (node (ref "J3") (pin "53") (pinfunction "MNT_1_53") (pintype "passive"))
      (node (ref "J3") (pin "54") (pinfunction "MNT_2_54") (pintype "passive"))
      (node (ref "J3") (pin "9") (pinfunction "9_9") (pintype "passive"))
      (node (ref "J4") (pin "15") (pinfunction "15_15") (pintype "passive"))
      (node (ref "J4") (pin "18") (pinfunction "18_18") (pintype "passive"))
      (node (ref "J4") (pin "21") (pinfunction "21_21") (pintype "passive"))
      (node (ref "J4") (pin "26") (pinfunction "26_26") (pintype "passive"))
      (node (ref "J4") (pin "27") (pinfunction "27_27") (pintype "passive"))
      (node (ref "J4") (pin "29") (pinfunction "29_29") (pintype "passive"))
      (node (ref "J4") (pin "34") (pinfunction "34_34") (pintype "passive"))
      (node (ref "J4") (pin "35") (pinfunction "35_35") (pintype "passive"))
      (node (ref "J4") (pin "37") (pinfunction "37_37") (pintype "passive"))
      (node (ref "J4") (pin "4") (pinfunction "4_4") (pintype "passive"))
      (node (ref "J4") (pin "40") (pinfunction "40_40") (pintype "passive"))
      (node (ref "J4") (pin "43") (pinfunction "43_43") (pintype "passive"))
      (node (ref "J4") (pin "50") (pinfunction "50_50") (pintype "passive"))
      (node (ref "J4") (pin "53") (pinfunction "MNT_1_53") (pintype "passive"))
      (node (ref "J4") (pin "54") (pinfunction "MNT_2_54") (pintype "passive"))
      (node (ref "J4") (pin "9") (pinfunction "9_9") (pintype "passive"))
      (node (ref "J7") (pin "1") (pinfunction "1_1") (pintype "passive"))
      (node (ref "J8") (pin "1") (pinfunction "1_1") (pintype "passive"))
      (node (ref "J9") (pin "15") (pinfunction "15_15") (pintype "passive"))
      (node (ref "J9") (pin "18") (pinfunction "18_18") (pintype "passive"))
      (node (ref "J9") (pin "21") (pinfunction "21_21") (pintype "passive"))
      (node (ref "J9") (pin "26") (pinfunction "26_26") (pintype "passive"))
      (node (ref "J9") (pin "27") (pinfunction "27_27") (pintype "passive"))
      (node (ref "J9") (pin "29") (pinfunction "29_29") (pintype "passive"))
      (node (ref "J9") (pin "34") (pinfunction "34_34") (pintype "passive"))
      (node (ref "J9") (pin "35") (pinfunction "35_35") (pintype "passive"))
      (node (ref "J9") (pin "37") (pinfunction "37_37") (pintype "passive"))
      (node (ref "J9") (pin "4") (pinfunction "4_4") (pintype "passive"))
      (node (ref "J9") (pin "40") (pinfunction "40_40") (pintype "passive"))
      (node (ref "J9") (pin "43") (pinfunction "43_43") (pintype "passive"))
      (node (ref "J9") (pin "50") (pinfunction "50_50") (pintype "passive"))
      (node (ref "J9") (pin "53") (pinfunction "MNT_1_53") (pintype "passive"))
      (node (ref "J9") (pin "54") (pinfunction "MNT_2_54") (pintype "passive"))
      (node (ref "J9") (pin "9") (pinfunction "9_9") (pintype "passive"))
      (node (ref "X1") (pin "6") (pinfunction "6_6") (pintype "passive"))
      (node (ref "X2") (pin "6") (pinfunction "6_6") (pintype "passive"))
      (node (ref "X3") (pin "6") (pinfunction "6_6") (pintype "passive"))
      (node (ref "X4") (pin "6") (pinfunction "6_6") (pintype "passive"))
    )
    (net (code "121") (name "Net-(LED1-Pad3)") (class "Default")
      (node (ref "LED1") (pin "3") (pinfunction "3_3") (pintype "power_in"))
      (node (ref "R14") (pin "1") (pinfunction "1_1") (pintype "passive"))
    )
    (net (code "122") (name "Net-(LED1-Pad4)") (class "Default")
      (node (ref "LED1") (pin "4") (pinfunction "4_4") (pintype "power_in"))
      (node (ref "R16") (pin "1") (pinfunction "1_1") (pintype "passive"))
    )
    (net (code "123") (name "Net-(LED2-Pad3)") (class "Default")
      (node (ref "LED2") (pin "3") (pinfunction "3_3") (pintype "power_in"))
      (node (ref "R15") (pin "1") (pinfunction "1_1") (pintype "passive"))
    )
    (net (code "124") (name "Net-(LED2-Pad4)") (class "Default")
      (node (ref "LED2") (pin "4") (pinfunction "4_4") (pintype "power_in"))
      (node (ref "R17") (pin "1") (pinfunction "1_1") (pintype "passive"))
    )
    (net (code "125") (name "Net-(LED3-Pad3)") (class "Default")
      (node (ref "LED3") (pin "3") (pinfunction "3_3") (pintype "power_in"))
      (node (ref "R20") (pin "1") (pinfunction "1_1") (pintype "passive"))
    )
    (net (code "126") (name "Net-(LED3-Pad4)") (class "Default")
      (node (ref "LED3") (pin "4") (pinfunction "4_4") (pintype "power_in"))
      (node (ref "R22") (pin "1") (pinfunction "1_1") (pintype "passive"))
    )
    (net (code "127") (name "Net-(LED4-Pad3)") (class "Default")
      (node (ref "LED4") (pin "3") (pinfunction "3_3") (pintype "power_in"))
      (node (ref "R21") (pin "1") (pinfunction "1_1") (pintype "passive"))
    )
    (net (code "128") (name "Net-(LED4-Pad4)") (class "Default")
      (node (ref "LED4") (pin "4") (pinfunction "4_4") (pintype "power_in"))
      (node (ref "R23") (pin "1") (pinfunction "1_1") (pintype "passive"))
    )
    (net (code "129") (name "VCC1P5") (class "Default")
      (node (ref "J10") (pin "28") (pinfunction "28_28") (pintype "passive"))
      (node (ref "J10") (pin "48") (pinfunction "48_48") (pintype "passive"))
      (node (ref "J10") (pin "6") (pinfunction "6_6") (pintype "passive"))
      (node (ref "J3") (pin "28") (pinfunction "28_28") (pintype "passive"))
      (node (ref "J3") (pin "48") (pinfunction "48_48") (pintype "passive"))
      (node (ref "J3") (pin "6") (pinfunction "6_6") (pintype "passive"))
      (node (ref "J4") (pin "28") (pinfunction "28_28") (pintype "passive"))
      (node (ref "J4") (pin "48") (pinfunction "48_48") (pintype "passive"))
      (node (ref "J4") (pin "6") (pinfunction "6_6") (pintype "passive"))
      (node (ref "J9") (pin "28") (pinfunction "28_28") (pintype "passive"))
      (node (ref "J9") (pin "48") (pinfunction "48_48") (pintype "passive"))
      (node (ref "J9") (pin "6") (pinfunction "6_6") (pintype "passive"))
    )
    (net (code "130") (name "VCC3P3_1") (class "Default")
      (node (ref "J10") (pin "2") (pinfunction "2_2") (pintype "passive"))
      (node (ref "J10") (pin "24") (pinfunction "24_24") (pintype "passive"))
      (node (ref "J10") (pin "52") (pinfunction "52_52") (pintype "passive"))
      (node (ref "J3") (pin "2") (pinfunction "2_2") (pintype "passive"))
      (node (ref "J3") (pin "24") (pinfunction "24_24") (pintype "passive"))
      (node (ref "J3") (pin "52") (pinfunction "52_52") (pintype "passive"))
      (node (ref "J4") (pin "2") (pinfunction "2_2") (pintype "passive"))
      (node (ref "J4") (pin "24") (pinfunction "24_24") (pintype "passive"))
      (node (ref "J4") (pin "52") (pinfunction "52_52") (pintype "passive"))
      (node (ref "J9") (pin "2") (pinfunction "2_2") (pintype "passive"))
      (node (ref "J9") (pin "24") (pinfunction "24_24") (pintype "passive"))
      (node (ref "J9") (pin "52") (pinfunction "52_52") (pintype "passive"))
      (node (ref "LED1") (pin "1") (pinfunction "1_1") (pintype "power_in"))
      (node (ref "LED1") (pin "2") (pinfunction "2_2") (pintype "power_in"))
      (node (ref "LED2") (pin "1") (pinfunction "1_1") (pintype "power_in"))
      (node (ref "LED2") (pin "2") (pinfunction "2_2") (pintype "power_in"))
      (node (ref "LED3") (pin "1") (pinfunction "1_1") (pintype "power_in"))
      (node (ref "LED3") (pin "2") (pinfunction "2_2") (pintype "power_in"))
      (node (ref "LED4") (pin "1") (pinfunction "1_1") (pintype "power_in"))
      (node (ref "LED4") (pin "2") (pinfunction "2_2") (pintype "power_in"))
      (node (ref "X1") (pin "4") (pinfunction "4_4") (pintype "passive"))
      (node (ref "X2") (pin "4") (pinfunction "4_4") (pintype "passive"))
      (node (ref "X3") (pin "4") (pinfunction "4_4") (pintype "passive"))
      (node (ref "X4") (pin "4") (pinfunction "4_4") (pintype "passive"))
    )
    (net (code "131") (name "unconnected-(J3-Pad1)") (class "Default")
      (node (ref "J3") (pin "1") (pinfunction "1_1") (pintype "passive+no_connect"))
    )
    (net (code "132") (name "unconnected-(J3-Pad8)") (class "Default")
      (node (ref "J3") (pin "8") (pinfunction "8_8") (pintype "passive+no_connect"))
    )
    (net (code "133") (name "unconnected-(J3-Pad10)") (class "Default")
      (node (ref "J3") (pin "10") (pinfunction "10_10") (pintype "passive+no_connect"))
    )
    (net (code "134") (name "unconnected-(J3-Pad12)") (class "Default")
      (node (ref "J3") (pin "12") (pinfunction "12_12") (pintype "passive+no_connect"))
    )
    (net (code "135") (name "unconnected-(J3-Pad14)") (class "Default")
      (node (ref "J3") (pin "14") (pinfunction "14_14") (pintype "passive+no_connect"))
    )
    (net (code "136") (name "unconnected-(J3-Pad16)") (class "Default")
      (node (ref "J3") (pin "16") (pinfunction "16_16") (pintype "passive+no_connect"))
    )
    (net (code "137") (name "unconnected-(J3-Pad36)") (class "Default")
      (node (ref "J3") (pin "36") (pinfunction "36_36") (pintype "passive+no_connect"))
    )
    (net (code "138") (name "unconnected-(J3-Pad38)") (class "Default")
      (node (ref "J3") (pin "38") (pinfunction "38_38") (pintype "passive+no_connect"))
    )
    (net (code "139") (name "unconnected-(J4-Pad1)") (class "Default")
      (node (ref "J4") (pin "1") (pinfunction "1_1") (pintype "passive+no_connect"))
    )
    (net (code "140") (name "unconnected-(J4-Pad8)") (class "Default")
      (node (ref "J4") (pin "8") (pinfunction "8_8") (pintype "passive+no_connect"))
    )
    (net (code "141") (name "unconnected-(J4-Pad10)") (class "Default")
      (node (ref "J4") (pin "10") (pinfunction "10_10") (pintype "passive+no_connect"))
    )
    (net (code "142") (name "unconnected-(J4-Pad12)") (class "Default")
      (node (ref "J4") (pin "12") (pinfunction "12_12") (pintype "passive+no_connect"))
    )
    (net (code "143") (name "unconnected-(J4-Pad14)") (class "Default")
      (node (ref "J4") (pin "14") (pinfunction "14_14") (pintype "passive+no_connect"))
    )
    (net (code "144") (name "unconnected-(J4-Pad16)") (class "Default")
      (node (ref "J4") (pin "16") (pinfunction "16_16") (pintype "passive+no_connect"))
    )
    (net (code "145") (name "unconnected-(J4-Pad36)") (class "Default")
      (node (ref "J4") (pin "36") (pinfunction "36_36") (pintype "passive+no_connect"))
    )
    (net (code "146") (name "unconnected-(J4-Pad38)") (class "Default")
      (node (ref "J4") (pin "38") (pinfunction "38_38") (pintype "passive+no_connect"))
    )
    (net (code "147") (name "unconnected-(J9-Pad1)") (class "Default")
      (node (ref "J9") (pin "1") (pinfunction "1_1") (pintype "passive+no_connect"))
    )
    (net (code "148") (name "unconnected-(J9-Pad8)") (class "Default")
      (node (ref "J9") (pin "8") (pinfunction "8_8") (pintype "passive+no_connect"))
    )
    (net (code "149") (name "unconnected-(J9-Pad10)") (class "Default")
      (node (ref "J9") (pin "10") (pinfunction "10_10") (pintype "passive+no_connect"))
    )
    (net (code "150") (name "unconnected-(J9-Pad12)") (class "Default")
      (node (ref "J9") (pin "12") (pinfunction "12_12") (pintype "passive+no_connect"))
    )
    (net (code "151") (name "unconnected-(J9-Pad14)") (class "Default")
      (node (ref "J9") (pin "14") (pinfunction "14_14") (pintype "passive+no_connect"))
    )
    (net (code "152") (name "unconnected-(J9-Pad16)") (class "Default")
      (node (ref "J9") (pin "16") (pinfunction "16_16") (pintype "passive+no_connect"))
    )
    (net (code "153") (name "unconnected-(J9-Pad36)") (class "Default")
      (node (ref "J9") (pin "36") (pinfunction "36_36") (pintype "passive+no_connect"))
    )
    (net (code "154") (name "unconnected-(J9-Pad38)") (class "Default")
      (node (ref "J9") (pin "38") (pinfunction "38_38") (pintype "passive+no_connect"))
    )
    (net (code "155") (name "unconnected-(J10-Pad1)") (class "Default")
      (node (ref "J10") (pin "1") (pinfunction "1_1") (pintype "passive+no_connect"))
    )
    (net (code "156") (name "unconnected-(J10-Pad8)") (class "Default")
      (node (ref "J10") (pin "8") (pinfunction "8_8") (pintype "passive+no_connect"))
    )
    (net (code "157") (name "unconnected-(J10-Pad10)") (class "Default")
      (node (ref "J10") (pin "10") (pinfunction "10_10") (pintype "passive+no_connect"))
    )
    (net (code "158") (name "unconnected-(J10-Pad12)") (class "Default")
      (node (ref "J10") (pin "12") (pinfunction "12_12") (pintype "passive+no_connect"))
    )
    (net (code "159") (name "unconnected-(J10-Pad14)") (class "Default")
      (node (ref "J10") (pin "14") (pinfunction "14_14") (pintype "passive+no_connect"))
    )
    (net (code "160") (name "unconnected-(J10-Pad16)") (class "Default")
      (node (ref "J10") (pin "16") (pinfunction "16_16") (pintype "passive+no_connect"))
    )
    (net (code "161") (name "unconnected-(J10-Pad36)") (class "Default")
      (node (ref "J10") (pin "36") (pinfunction "36_36") (pintype "passive+no_connect"))
    )
    (net (code "162") (name "unconnected-(J10-Pad38)") (class "Default")
      (node (ref "J10") (pin "38") (pinfunction "38_38") (pintype "passive+no_connect"))
    )
  )
)
